# SD.net
KiCad netlist of a schematic drawn in Altium Designer
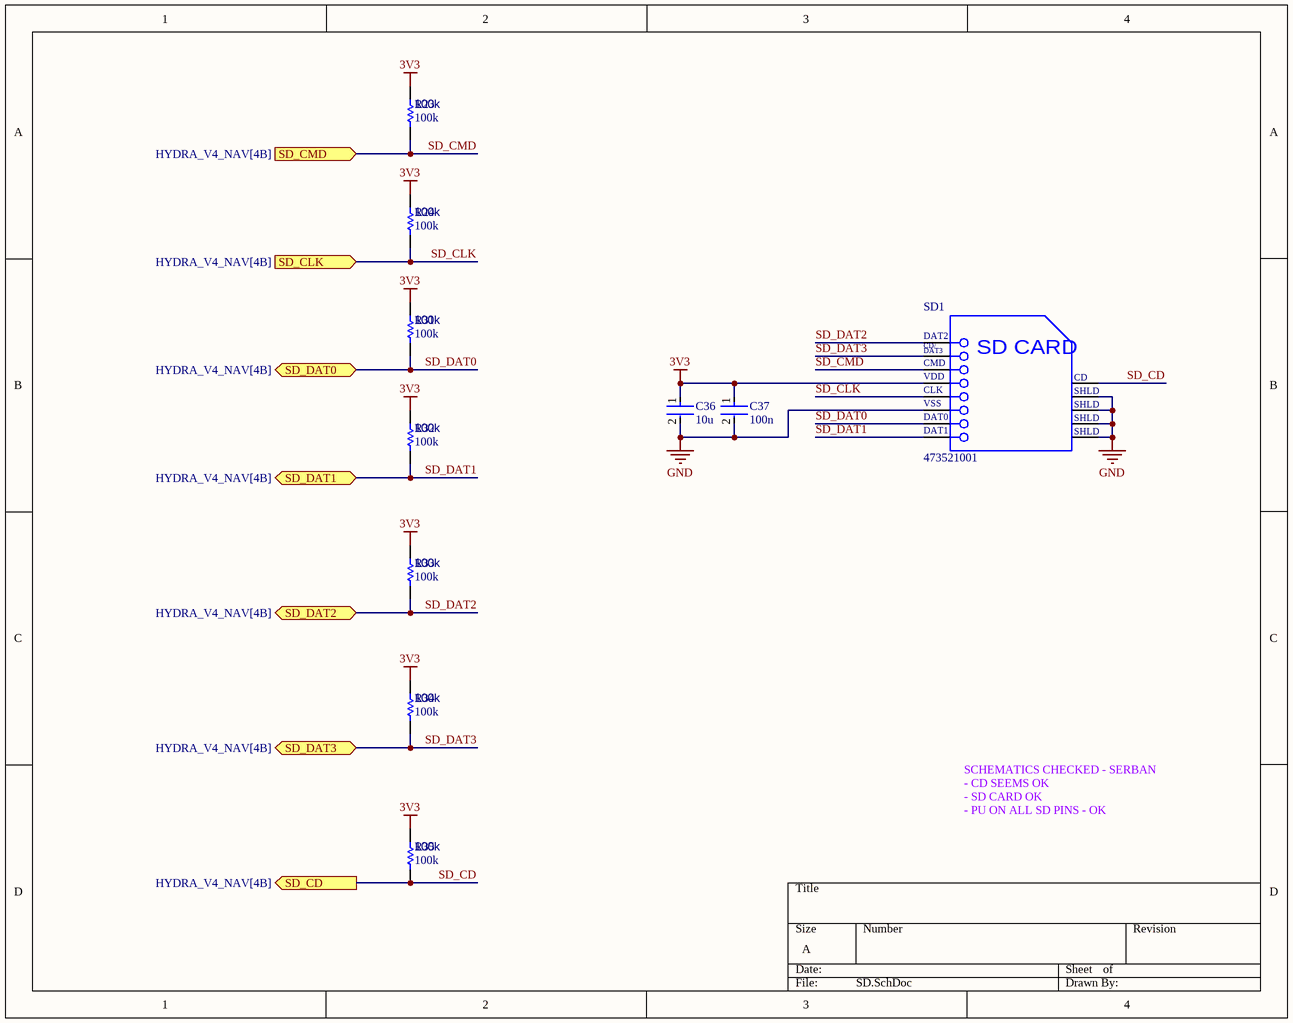
[diagram p0: SD.SchDoc]

(export (version "E")
  (design (tool "Eeschema 10.0.6"))
  (components
    (comp (ref "C36")
      (value "10u")
      (footprint "FP-0402-L_1_0_0_05-W_0_5-IPC_A")
      (description "LARGE PADS, 0402 CAP, CHANGE COMMENT TO MATCH REAL P/N")
      (libsource (lib "Space Concordia") (part "b4654b650e69147ec39a6b967a45e02"))
    )
    (comp (ref "C37")
      (value "100n")
      (footprint "FP-0402-L_1_0_0_05-W_0_5-IPC_A")
      (description "LARGE PADS, 0402 CAP, CHANGE COMMENT TO MATCH REAL P/N")
      (libsource (lib "Space Concordia") (part "b4654b650e69147ec39a6b967a45e02"))
    )
    (comp (ref "R23")
      (value "100k")
      (footprint "R0603B")
      (description "Resistor")
      (fields (field (name "ALTIUM_VALUE") "100k"))
      (libsource (lib "Space Concordia") (part "Resistor"))
    )
    (comp (ref "R24")
      (value "100k")
      (footprint "R0603B")
      (description "Resistor")
      (fields (field (name "ALTIUM_VALUE") "100k"))
      (libsource (lib "Space Concordia") (part "Resistor"))
    )
    (comp (ref "R31")
      (value "100k")
      (footprint "R0603B")
      (description "Resistor")
      (fields (field (name "ALTIUM_VALUE") "100k"))
      (libsource (lib "Space Concordia") (part "Resistor"))
    )
    (comp (ref "R32")
      (value "100k")
      (footprint "R0603B")
      (description "Resistor")
      (fields (field (name "ALTIUM_VALUE") "100k"))
      (libsource (lib "Space Concordia") (part "Resistor"))
    )
    (comp (ref "R33")
      (value "100k")
      (footprint "R0603B")
      (description "Resistor")
      (fields (field (name "ALTIUM_VALUE") "100k"))
      (libsource (lib "Space Concordia") (part "Resistor"))
    )
    (comp (ref "R34")
      (value "100k")
      (footprint "R0603B")
      (description "Resistor")
      (fields (field (name "ALTIUM_VALUE") "100k"))
      (libsource (lib "Space Concordia") (part "Resistor"))
    )
    (comp (ref "R35")
      (value "100k")
      (footprint "R0603B")
      (description "Resistor")
      (fields (field (name "ALTIUM_VALUE") "100k"))
      (libsource (lib "Space Concordia") (part "Resistor"))
    )
    (comp (ref "SD1")
      (value "473521001")
      (footprint "MOLX-473521001_V")
      (description "MicroSD(TM), Pitch 1.1 mm, 8 Position, Height 1.88 mm, -20 to 85 degC, RoHS, Tape and Reel")
      (fields (field (name "MANUFACTURER") "Molex"))
      (libsource (lib "Altium Content Vault") (part "CN-SD-8-1SW-4S"))
    )
  )
  (nets
    (net (code "1") (name "/SD_CD") (class "Default")
      (node (ref "R35") (pin "2") (pinfunction "2_2") (pintype "passive"))
      (node (ref "SD1") (pin "9") (pinfunction "CD_9") (pintype "passive"))
    )
    (net (code "2") (name "/SD_CLK") (class "Default")
      (node (ref "R24") (pin "2") (pinfunction "2_2") (pintype "passive"))
      (node (ref "SD1") (pin "5") (pinfunction "CLK_5") (pintype "passive"))
    )
    (net (code "3") (name "/SD_CMD") (class "Default")
      (node (ref "R23") (pin "2") (pinfunction "2_2") (pintype "passive"))
      (node (ref "SD1") (pin "3") (pinfunction "CMD_3") (pintype "passive"))
    )
    (net (code "4") (name "/SD_DAT0") (class "Default")
      (node (ref "R31") (pin "2") (pinfunction "2_2") (pintype "passive"))
      (node (ref "SD1") (pin "7") (pinfunction "DAT0_7") (pintype "passive"))
    )
    (net (code "5") (name "/SD_DAT1") (class "Default")
      (node (ref "R32") (pin "2") (pinfunction "2_2") (pintype "passive"))
      (node (ref "SD1") (pin "8") (pinfunction "DAT1_8") (pintype "passive"))
    )
    (net (code "6") (name "/SD_DAT2") (class "Default")
      (node (ref "R33") (pin "2") (pinfunction "2_2") (pintype "passive"))
      (node (ref "SD1") (pin "1") (pinfunction "DAT2_1") (pintype "passive"))
    )
    (net (code "7") (name "/SD_DAT3") (class "Default")
      (node (ref "R34") (pin "2") (pinfunction "2_2") (pintype "passive"))
      (node (ref "SD1") (pin "2") (pinfunction "CD/DAT3_2") (pintype "passive"))
    )
    (net (code "8") (name "3V3") (class "Default")
      (node (ref "C36") (pin "1") (pinfunction "1_1") (pintype "passive"))
      (node (ref "C37") (pin "1") (pinfunction "1_1") (pintype "passive"))
      (node (ref "R23") (pin "1") (pinfunction "1_1") (pintype "passive"))
      (node (ref "R24") (pin "1") (pinfunction "1_1") (pintype "passive"))
      (node (ref "R31") (pin "1") (pinfunction "1_1") (pintype "passive"))
      (node (ref "R32") (pin "1") (pinfunction "1_1") (pintype "passive"))
      (node (ref "R33") (pin "1") (pinfunction "1_1") (pintype "passive"))
      (node (ref "R34") (pin "1") (pinfunction "1_1") (pintype "passive"))
      (node (ref "R35") (pin "1") (pinfunction "1_1") (pintype "passive"))
      (node (ref "SD1") (pin "4") (pinfunction "VDD_4") (pintype "passive"))
    )
    (net (code "9") (name "GND") (class "Default")
      (node (ref "C36") (pin "2") (pinfunction "2_2") (pintype "passive"))
      (node (ref "C37") (pin "2") (pinfunction "2_2") (pintype "passive"))
      (node (ref "SD1") (pin "10") (pinfunction "SHLD_10") (pintype "passive"))
      (node (ref "SD1") (pin "11") (pinfunction "SHLD_11") (pintype "passive"))
      (node (ref "SD1") (pin "12") (pinfunction "SHLD_12") (pintype "passive"))
      (node (ref "SD1") (pin "13") (pinfunction "SHLD_13") (pintype "passive"))
      (node (ref "SD1") (pin "6") (pinfunction "VSS_6") (pintype "passive"))
    )
  )
)
